# 3_3V_Regulator.net
KiCad netlist of a schematic drawn in Altium Designer
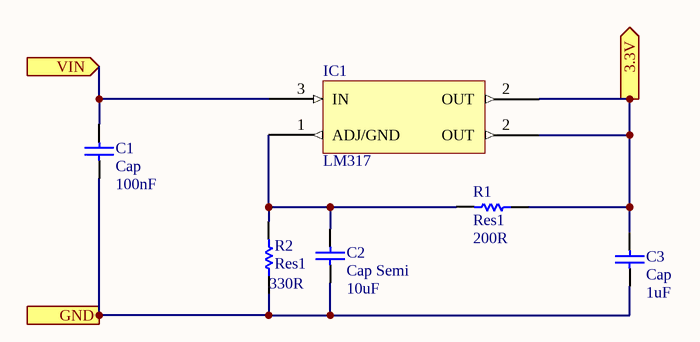
[diagram p0: 3.3V_Regulator.SchDoc]

(export (version "E")
  (design (tool "Eeschema 10.0.6"))
  (components
    (comp (ref "C1")
      (value "Cap")
      (footprint "0402")
      (description "Multilayer Ceramic Capacitors MLCC - SMD/SMT 16volts 0.1uF 20% X7R")
      (fields (field (name "ALTIUM_VALUE") "100nF"))
      (libsource (lib "Miscellaneous Devices") (part "Cap"))
    )
    (comp (ref "C2")
      (value "Cap Semi")
      (footprint "CAP_TANT1206")
      (description "Tantalum Capacitors - Solid SMD 16V 10uF 1206 10% ESR=3Ohms")
      (fields (field (name "ALTIUM_VALUE") "10uF"))
      (libsource (lib "Miscellaneous Devices") (part "Cap Semi"))
    )
    (comp (ref "C3")
      (value "Cap")
      (footprint "CAP_TANT1206")
      (description "Tantalum Capacitors - Solid SMD 20V 1.0uF 1206 10% ESR=9Ohms")
      (fields (field (name "ALTIUM_VALUE") "1uF"))
      (libsource (lib "Miscellaneous Devices") (part "Cap"))
    )
    (comp (ref "IC1")
      (value "LM317")
      (footprint "SOT-223")
      (libsource (lib "MainboardSchLib") (part "LM317"))
    )
    (comp (ref "R1")
      (value "Res1")
      (footprint "RES0402")
      (description "Thick Film Resistors - SMD 1/16watt 200ohms 5%")
      (fields (field (name "ALTIUM_VALUE") "200R"))
      (libsource (lib "Miscellaneous Devices") (part "Res1"))
    )
    (comp (ref "R2")
      (value "Res1")
      (footprint "RES0402")
      (description "Thick Film Resistors - SMD 0.2watt 330ohms 1% 100ppm")
      (fields (field (name "ALTIUM_VALUE") "330R"))
      (libsource (lib "Miscellaneous Devices") (part "Res1"))
    )
  )
  (nets
    (net (code "1") (name "/3.3V") (class "Default")
      (node (ref "C3") (pin "2") (pinfunction "2_2") (pintype "passive"))
      (node (ref "IC1") (pin "2") (pinfunction "OUT_2") (pintype "output"))
      (node (ref "R1") (pin "1") (pinfunction "1_1") (pintype "passive"))
    )
    (net (code "2") (name "/GND") (class "Default")
      (node (ref "C1") (pin "1") (pinfunction "1_1") (pintype "passive"))
      (node (ref "C2") (pin "1") (pinfunction "1_1") (pintype "passive"))
      (node (ref "C3") (pin "1") (pinfunction "1_1") (pintype "passive"))
      (node (ref "R2") (pin "1") (pinfunction "1_1") (pintype "passive"))
    )
    (net (code "3") (name "/VIN") (class "Default")
      (node (ref "C1") (pin "2") (pinfunction "2_2") (pintype "passive"))
      (node (ref "IC1") (pin "3") (pinfunction "IN_3") (pintype "input"))
    )
    (net (code "4") (name "Net-(IC1-ADJ{slash}GND)") (class "Default")
      (node (ref "C2") (pin "2") (pinfunction "2_2") (pintype "passive"))
      (node (ref "IC1") (pin "1") (pinfunction "ADJ/GND_1") (pintype "output"))
      (node (ref "R1") (pin "2") (pinfunction "2_2") (pintype "passive"))
      (node (ref "R2") (pin "2") (pinfunction "2_2") (pintype "passive"))
    )
  )
)
